# Sensors.net
KiCad netlist of a schematic drawn in Altium Designer
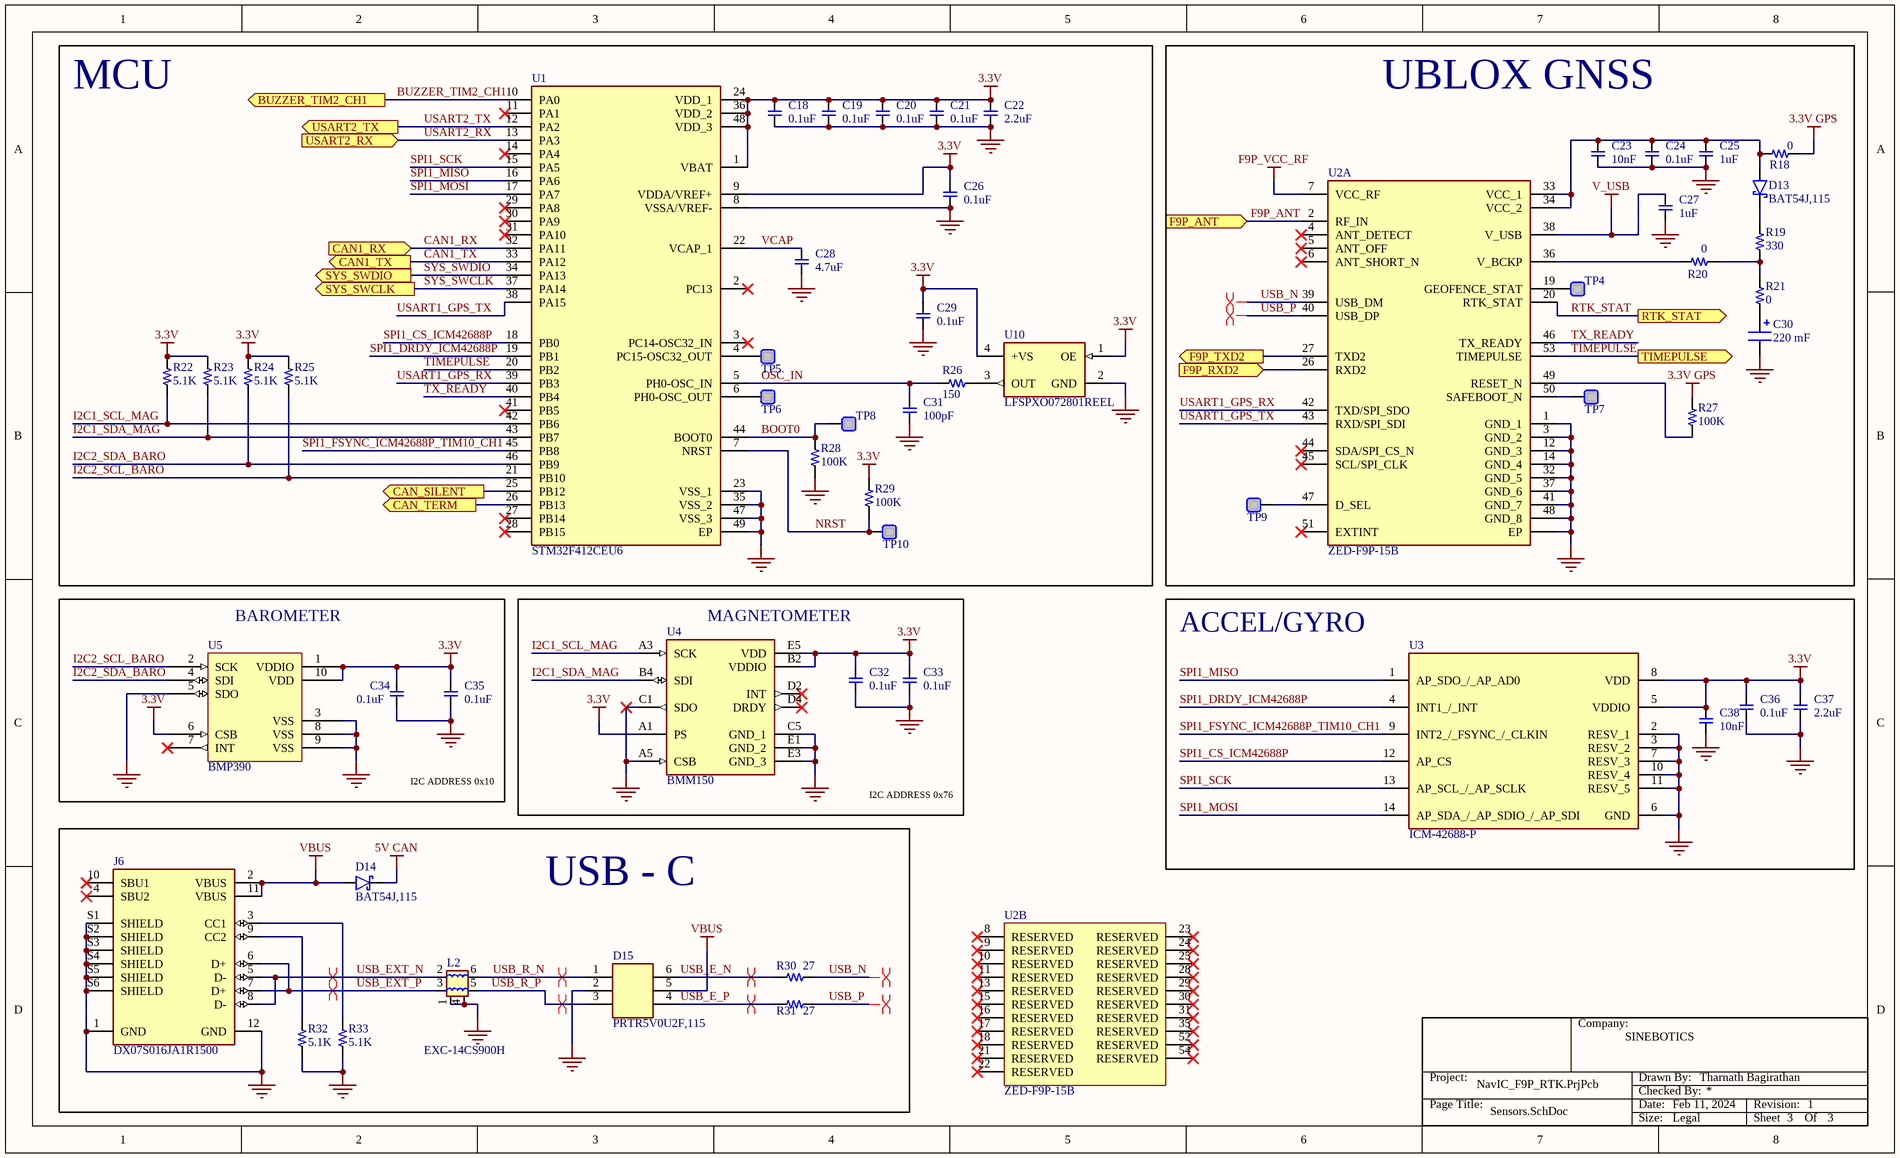
[diagram p0: Sensors.SchDoc]

(export (version "E")
  (design (tool "Eeschema 10.0.6"))
  (components
    (comp (ref "C18")
      (value "0.1uF")
      (footprint "C0402")
      (description "Capacitor 0402 Generic")
      (fields
        (field (name "MANUFACTURER PART NUMBER") "0402X104K250CT")
        (field (name "MANUFACTURER") "Walsin Technology Corporation")
      )
      (libsource (lib "Library") (part "CAP_0402"))
    )
    (comp (ref "C19")
      (value "0.1uF")
      (footprint "C0402")
      (description "Capacitor 0402 Generic")
      (fields
        (field (name "MANUFACTURER PART NUMBER") "0402X104K250CT")
        (field (name "MANUFACTURER") "Walsin Technology Corporation")
      )
      (libsource (lib "Library") (part "CAP_0402"))
    )
    (comp (ref "C20")
      (value "0.1uF")
      (footprint "C0402")
      (description "Capacitor 0402 Generic")
      (fields
        (field (name "MANUFACTURER PART NUMBER") "0402X104K250CT")
        (field (name "MANUFACTURER") "Walsin Technology Corporation")
      )
      (libsource (lib "Library") (part "CAP_0402"))
    )
    (comp (ref "C21")
      (value "0.1uF")
      (footprint "C0402")
      (description "Capacitor 0402 Generic")
      (fields
        (field (name "MANUFACTURER PART NUMBER") "0402X104K250CT")
        (field (name "MANUFACTURER") "Walsin Technology Corporation")
      )
      (libsource (lib "Library") (part "CAP_0402"))
    )
    (comp (ref "C22")
      (value "2.2uF")
      (footprint "C0402")
      (description "Capacitor 0402 Generic")
      (fields
        (field (name "MANUFACTURER PART NUMBER") "GRM155R61A225ME95D")
        (field (name "MANUFACTURER") "Murata")
      )
      (libsource (lib "Library") (part "CAP_0402"))
    )
    (comp (ref "C23")
      (value "10nF")
      (footprint "C0402")
      (description "Capacitor 0402 Generic")
      (fields
        (field (name "MANUFACTURER PART NUMBER") "CL05B103KA5NNNC")
        (field (name "MANUFACTURER") "Samsung")
      )
      (libsource (lib "Library") (part "CAP_0402"))
    )
    (comp (ref "C24")
      (value "0.1uF")
      (footprint "C0402")
      (description "Capacitor 0402 Generic")
      (fields
        (field (name "MANUFACTURER PART NUMBER") "0402X104K250CT")
        (field (name "MANUFACTURER") "Walsin Technology Corporation")
      )
      (libsource (lib "Library") (part "CAP_0402"))
    )
    (comp (ref "C25")
      (value "1uF")
      (footprint "C0402")
      (description "Capacitor 0402 Generic")
      (fields
        (field (name "MANUFACTURER PART NUMBER") "CL05A105KP5NNNC")
        (field (name "MANUFACTURER") "Samsung Electro-Mechanics")
      )
      (libsource (lib "Library") (part "CAP_0402"))
    )
    (comp (ref "C26")
      (value "0.1uF")
      (footprint "C0402")
      (description "Capacitor 0402 Generic")
      (fields
        (field (name "MANUFACTURER PART NUMBER") "0402X104K250CT")
        (field (name "MANUFACTURER") "Walsin Technology Corporation")
      )
      (libsource (lib "Library") (part "CAP_0402"))
    )
    (comp (ref "C27")
      (value "1uF")
      (footprint "C0402")
      (description "Capacitor 0402 Generic")
      (fields
        (field (name "MANUFACTURER PART NUMBER") "CL05A105KP5NNNC")
        (field (name "MANUFACTURER") "Samsung Electro-Mechanics")
      )
      (libsource (lib "Library") (part "CAP_0402"))
    )
    (comp (ref "C28")
      (value "4.7uF")
      (footprint "C0402")
      (description "Capacitor 0402 Generic")
      (fields
        (field (name "MANUFACTURER PART NUMBER") "C1005X5R0J475K050BC")
        (field (name "MANUFACTURER") "TDK Corporation")
      )
      (libsource (lib "Library") (part "CAP_0402"))
    )
    (comp (ref "C29")
      (value "0.1uF")
      (footprint "C0402")
      (description "Capacitor 0402 Generic")
      (fields
        (field (name "MANUFACTURER PART NUMBER") "0402X104K250CT")
        (field (name "MANUFACTURER") "Walsin Technology Corporation")
      )
      (libsource (lib "Library") (part "CAP_0402"))
    )
    (comp (ref "C30")
      (value "220 mF")
      (footprint "SamacSys:DSK3R3H334THL")
      (description "Capacitor Polarised")
      (fields (field (name "MANUFACTURER PART NUMBER") "DSK-3R3H224U-HL"))
      (libsource (lib "SamacSys") (part "DSK-3R3H224U-HL"))
    )
    (comp (ref "C31")
      (value "100pF")
      (footprint "C0402")
      (description "Capacitor 0402 Generic")
      (fields
        (field (name "MANUFACTURER PART NUMBER") "CL05C101JB5NNNC")
        (field (name "MANUFACTURER") "Samsung Electro-Mechanics")
      )
      (libsource (lib "Library") (part "CAP_0402"))
    )
    (comp (ref "C32")
      (value "0.1uF")
      (footprint "C0402")
      (description "Capacitor 0402 Generic")
      (fields
        (field (name "MANUFACTURER PART NUMBER") "0402X104K250CT")
        (field (name "MANUFACTURER") "Walsin Technology Corporation")
      )
      (libsource (lib "Library") (part "CAP_0402"))
    )
    (comp (ref "C33")
      (value "0.1uF")
      (footprint "C0402")
      (description "Capacitor 0402 Generic")
      (fields
        (field (name "MANUFACTURER PART NUMBER") "0402X104K250CT")
        (field (name "MANUFACTURER") "Walsin Technology Corporation")
      )
      (libsource (lib "Library") (part "CAP_0402"))
    )
    (comp (ref "C34")
      (value "0.1uF")
      (footprint "C0402")
      (description "Capacitor 0402 Generic")
      (fields
        (field (name "MANUFACTURER PART NUMBER") "0402X104K250CT")
        (field (name "MANUFACTURER") "Walsin Technology Corporation")
      )
      (libsource (lib "Library") (part "CAP_0402"))
    )
    (comp (ref "C35")
      (value "0.1uF")
      (footprint "C0402")
      (description "Capacitor 0402 Generic")
      (fields
        (field (name "MANUFACTURER PART NUMBER") "0402X104K250CT")
        (field (name "MANUFACTURER") "Walsin Technology Corporation")
      )
      (libsource (lib "Library") (part "CAP_0402"))
    )
    (comp (ref "C36")
      (value "0.1uF")
      (footprint "C0402")
      (description "Capacitor 0402 Generic")
      (fields
        (field (name "MANUFACTURER PART NUMBER") "0402X104K250CT")
        (field (name "MANUFACTURER") "Walsin Technology Corporation")
      )
      (libsource (lib "Library") (part "CAP_0402"))
    )
    (comp (ref "C37")
      (value "2.2uF")
      (footprint "C0402")
      (description "Capacitor 0402 Generic")
      (fields
        (field (name "MANUFACTURER PART NUMBER") "GRM155R61A225ME95D")
        (field (name "MANUFACTURER") "Murata")
      )
      (libsource (lib "Library") (part "CAP_0402"))
    )
    (comp (ref "C38")
      (value "10nF")
      (footprint "C0402")
      (description "Capacitor 0402 Generic")
      (fields
        (field (name "MANUFACTURER PART NUMBER") "CL05B103KA5NNNC")
        (field (name "MANUFACTURER") "Samsung")
      )
      (libsource (lib "Library") (part "CAP_0402"))
    )
    (comp (ref "D13")
      (value "BAT54J,115")
      (footprint "SamacSys:SODFL2512X80N")
      (description "Schottky Diode")
      (libsource (lib "SamacSys") (part "BAT54J,115"))
    )
    (comp (ref "D14")
      (value "BAT54J,115")
      (footprint "SamacSys:SODFL2512X80N")
      (description "Schottky Diode")
      (libsource (lib "SamacSys") (part "BAT54J,115"))
    )
    (comp (ref "D15")
      (value "PRTR5V0U2F,115")
      (footprint "SamacSys:PESD3V3L5UF115")
      (description "Diode")
      (libsource (lib "SamacSys") (part "PRTR5V0U2F,115"))
    )
    (comp (ref "J6")
      (value "DX07S016JA1R1500")
      (footprint "JAE_DX07S016JA1R1500")
      (libsource (lib "Schlib") (part "DX07S016JA1R1500"))
    )
    (comp (ref "L2")
      (value "EXC-14CS900H")
      (footprint "SamacSys:EXC14CS900H")
      (description "Filter")
      (libsource (lib "SamacSys") (part "EXC-14CS900H"))
    )
    (comp (ref "R18")
      (value "0")
      (footprint "R0402")
      (description "Resistor 0402 Generic")
      (fields
        (field (name "MANUFACTURER") "Yageo")
        (field (name "MANUFACTURER PART NUMBER") "AC0402JR-070RL")
      )
      (libsource (lib "Library") (part "RES_0402"))
    )
    (comp (ref "R19")
      (value "330")
      (footprint "R0402")
      (description "Resistor 0402 Generic")
      (fields
        (field (name "MANUFACTURER") "Yageo")
        (field (name "MANUFACTURER PART NUMBER") "RC0402FR-07330RL")
      )
      (libsource (lib "Library") (part "RES_0402"))
    )
    (comp (ref "R20")
      (value "0")
      (footprint "R0402")
      (description "Resistor 0402 Generic")
      (fields
        (field (name "MANUFACTURER") "Yageo")
        (field (name "MANUFACTURER PART NUMBER") "AC0402JR-070RL")
      )
      (libsource (lib "Library") (part "RES_0402"))
    )
    (comp (ref "R21")
      (value "0")
      (footprint "R0402")
      (description "Resistor 0402 Generic")
      (fields
        (field (name "MANUFACTURER") "Yageo")
        (field (name "MANUFACTURER PART NUMBER") "AC0402JR-070RL")
      )
      (libsource (lib "Library") (part "RES_0402"))
    )
    (comp (ref "R22")
      (value "5.1K")
      (footprint "R0402")
      (description "Resistor 0402 Generic")
      (fields
        (field (name "MANUFACTURER") "Yageo")
        (field (name "MANUFACTURER PART NUMBER") "RC0402FR-075K1L")
      )
      (libsource (lib "Library") (part "RES_0402"))
    )
    (comp (ref "R23")
      (value "5.1K")
      (footprint "R0402")
      (description "Resistor 0402 Generic")
      (fields
        (field (name "MANUFACTURER") "Yageo")
        (field (name "MANUFACTURER PART NUMBER") "RC0402FR-075K1L")
      )
      (libsource (lib "Library") (part "RES_0402"))
    )
    (comp (ref "R24")
      (value "5.1K")
      (footprint "R0402")
      (description "Resistor 0402 Generic")
      (fields
        (field (name "MANUFACTURER") "Yageo")
        (field (name "MANUFACTURER PART NUMBER") "RC0402FR-075K1L")
      )
      (libsource (lib "Library") (part "RES_0402"))
    )
    (comp (ref "R25")
      (value "5.1K")
      (footprint "R0402")
      (description "Resistor 0402 Generic")
      (fields
        (field (name "MANUFACTURER") "Yageo")
        (field (name "MANUFACTURER PART NUMBER") "RC0402FR-075K1L")
      )
      (libsource (lib "Library") (part "RES_0402"))
    )
    (comp (ref "R26")
      (value "150")
      (footprint "R0402")
      (description "Resistor 0402 Generic")
      (fields
        (field (name "MANUFACTURER") "Stackpole Electronics Inc")
        (field (name "MANUFACTURER PART NUMBER") "RC0402FR-07150RL")
      )
      (libsource (lib "Library") (part "RES_0402"))
    )
    (comp (ref "R27")
      (value "100K")
      (footprint "R0402")
      (description "Resistor 0402 Generic")
      (fields
        (field (name "MANUFACTURER") "Yageo")
        (field (name "MANUFACTURER PART NUMBER") "AC0402JR-07100KL")
      )
      (libsource (lib "Library") (part "RES_0402"))
    )
    (comp (ref "R28")
      (value "100K")
      (footprint "R0402")
      (description "Resistor 0402 Generic")
      (fields
        (field (name "MANUFACTURER") "Yageo")
        (field (name "MANUFACTURER PART NUMBER") "AC0402JR-07100KL")
      )
      (libsource (lib "Library") (part "RES_0402"))
    )
    (comp (ref "R29")
      (value "100K")
      (footprint "R0402")
      (description "Resistor 0402 Generic")
      (fields
        (field (name "MANUFACTURER") "Yageo")
        (field (name "MANUFACTURER PART NUMBER") "AC0402JR-07100KL")
      )
      (libsource (lib "Library") (part "RES_0402"))
    )
    (comp (ref "R30")
      (value "27")
      (footprint "R0402")
      (description "Resistor 0402 Generic")
      (fields
        (field (name "MANUFACTURER") "Yageo")
        (field (name "MANUFACTURER PART NUMBER") "AC0402FR-0727RL")
      )
      (libsource (lib "Library") (part "RES_0402"))
    )
    (comp (ref "R31")
      (value "27")
      (footprint "R0402")
      (description "Resistor 0402 Generic")
      (fields
        (field (name "MANUFACTURER") "Yageo")
        (field (name "MANUFACTURER PART NUMBER") "AC0402FR-0727RL")
      )
      (libsource (lib "Library") (part "RES_0402"))
    )
    (comp (ref "R32")
      (value "5.1K")
      (footprint "R0402")
      (description "Resistor 0402 Generic")
      (fields
        (field (name "MANUFACTURER") "Yageo")
        (field (name "MANUFACTURER PART NUMBER") "RC0402FR-075K1L")
      )
      (libsource (lib "Library") (part "RES_0402"))
    )
    (comp (ref "R33")
      (value "5.1K")
      (footprint "R0402")
      (description "Resistor 0402 Generic")
      (fields
        (field (name "MANUFACTURER") "Yageo")
        (field (name "MANUFACTURER PART NUMBER") "RC0402FR-075K1L")
      )
      (libsource (lib "Library") (part "RES_0402"))
    )
    (comp (ref "TP4")
      (value "TestPad")
      (footprint "TestPad")
      (description "Test Pads")
      (libsource (lib "Schlib") (part "TestPad"))
    )
    (comp (ref "TP5")
      (value "TestPad")
      (footprint "TestPad")
      (description "Test Pads")
      (libsource (lib "Schlib") (part "TestPad"))
    )
    (comp (ref "TP6")
      (value "TestPad")
      (footprint "TestPad")
      (description "Test Pads")
      (libsource (lib "Schlib") (part "TestPad"))
    )
    (comp (ref "TP7")
      (value "TestPad")
      (footprint "TestPad")
      (description "Test Pads")
      (libsource (lib "Schlib") (part "TestPad"))
    )
    (comp (ref "TP8")
      (value "TestPad")
      (footprint "TestPad")
      (description "Test Pads")
      (libsource (lib "Schlib") (part "TestPad"))
    )
    (comp (ref "TP9")
      (value "TestPad")
      (footprint "TestPad")
      (description "Test Pads")
      (libsource (lib "Schlib") (part "TestPad"))
    )
    (comp (ref "TP10")
      (value "TestPad")
      (footprint "TestPad")
      (description "Test Pads")
      (libsource (lib "Schlib") (part "TestPad"))
    )
    (comp (ref "U1")
      (value "STM32F412CEU6")
      (footprint "QFN50P700X700X65-49N-D")
      (description "ARM Microcontrollers - MCU 16/32-BITS MICROS")
      (libsource (lib "Schlib") (part "STM32F412CEU6"))
    )
    (comp (ref "U2")
      (value "ZED-F9P-15B")
      (footprint "ZEDF9P15B")
      (description "Ublox F9P-15B Dual Band GNSS Receiver")
      (libsource (lib "Schlib") (part "ZED-F9P-15B"))
    )
    (comp (ref "U3")
      (value "ICM-42688-P")
      (footprint "SamacSys:IIM42352")
      (description "Integrated Circuit")
      (libsource (lib "SamacSys") (part "ICM-42688-P"))
    )
    (comp (ref "U4")
      (value "BMM150")
      (footprint "SamacSys:BMM150")
      (description "Integrated Circuit")
      (libsource (lib "SamacSys") (part "BMM150"))
    )
    (comp (ref "U5")
      (value "BMP390")
      (footprint "BMP390")
      (description "Bosch Sensortec BMP390 Barometer")
      (fields (field (name "MANUFACTURER") "Bosch Sensortec"))
      (libsource (lib "Schlib") (part "BMP390"))
    )
    (comp (ref "U10")
      (value "LFSPXO072801REEL")
      (footprint "SamacSys:LFSPXO072801REEL")
      (description "Crystal or Oscillator")
      (libsource (lib "SamacSys") (part "LFSPXO072801REEL"))
    )
  )
  (nets
    (net (code "1") (name "/BOOT0") (class "Default")
      (node (ref "R28") (pin "2") (pintype "passive"))
      (node (ref "TP8") (pin "1") (pinfunction "1_1") (pintype "passive"))
      (node (ref "U1") (pin "44") (pinfunction "BOOT0_44") (pintype "passive"))
    )
    (net (code "2") (name "/BUZZER_TIM2_CH1") (class "Default")
      (node (ref "U1") (pin "10") (pinfunction "PA0_10") (pintype "passive"))
    )
    (net (code "3") (name "/CAN1_RX") (class "Default")
      (node (ref "U1") (pin "32") (pinfunction "PA11_32") (pintype "passive"))
    )
    (net (code "4") (name "/CAN1_TX") (class "Default")
      (node (ref "U1") (pin "33") (pinfunction "PA12_33") (pintype "passive"))
    )
    (net (code "5") (name "/CAN_SILENT") (class "Default")
      (node (ref "U1") (pin "25") (pinfunction "PB12_25") (pintype "passive"))
    )
    (net (code "6") (name "/CAN_TERM") (class "Default")
      (node (ref "U1") (pin "26") (pinfunction "PB13_26") (pintype "passive"))
    )
    (net (code "7") (name "/F9P_ANT") (class "Default")
      (node (ref "U2") (pin "2") (pinfunction "RF_IN_2") (pintype "passive"))
    )
    (net (code "8") (name "/F9P_RXD2") (class "Default")
      (node (ref "U2") (pin "26") (pinfunction "RXD2_26") (pintype "passive"))
    )
    (net (code "9") (name "/F9P_TXD2") (class "Default")
      (node (ref "U2") (pin "27") (pinfunction "TXD2_27") (pintype "passive"))
    )
    (net (code "10") (name "/I2C1_SCL_MAG") (class "Default")
      (node (ref "R22") (pin "1") (pintype "passive"))
      (node (ref "U1") (pin "42") (pinfunction "PB6_42") (pintype "passive"))
      (node (ref "U4") (pin "A3") (pinfunction "SCK_A3") (pintype "input"))
    )
    (net (code "11") (name "/I2C1_SDA_MAG") (class "Default")
      (node (ref "R23") (pin "1") (pintype "passive"))
      (node (ref "U1") (pin "43") (pinfunction "PB7_43") (pintype "passive"))
      (node (ref "U4") (pin "B4") (pinfunction "SDI_B4") (pintype "bidirectional"))
    )
    (net (code "12") (name "/I2C2_SCL_BARO") (class "Default")
      (node (ref "R25") (pin "1") (pintype "passive"))
      (node (ref "U1") (pin "21") (pinfunction "PB10_21") (pintype "passive"))
      (node (ref "U5") (pin "2") (pinfunction "SCK_2") (pintype "input"))
    )
    (net (code "13") (name "/I2C2_SDA_BARO") (class "Default")
      (node (ref "R24") (pin "1") (pintype "passive"))
      (node (ref "U1") (pin "46") (pinfunction "PB9_46") (pintype "passive"))
      (node (ref "U5") (pin "4") (pinfunction "SDI_4") (pintype "bidirectional"))
    )
    (net (code "14") (name "/NRST") (class "Default")
      (node (ref "R29") (pin "1") (pintype "passive"))
      (node (ref "TP10") (pin "1") (pinfunction "1_1") (pintype "passive"))
      (node (ref "U1") (pin "7") (pinfunction "NRST_7") (pintype "passive"))
    )
    (net (code "15") (name "/OSC_IN") (class "Default")
      (node (ref "C31") (pin "2") (pintype "passive"))
      (node (ref "R26") (pin "2") (pintype "passive"))
      (node (ref "U1") (pin "5") (pinfunction "PH0-OSC_IN_5") (pintype "passive"))
    )
    (net (code "16") (name "/RTK_STAT") (class "Default")
      (node (ref "U2") (pin "20") (pinfunction "RTK_STAT_20") (pintype "passive"))
    )
    (net (code "17") (name "/SPI1_CS_ICM42688P") (class "Default")
      (node (ref "U1") (pin "18") (pinfunction "PB0_18") (pintype "passive"))
      (node (ref "U3") (pin "12") (pinfunction "AP_CS_12") (pintype "passive"))
    )
    (net (code "18") (name "/SPI1_DRDY_ICM42688P") (class "Default")
      (node (ref "U1") (pin "19") (pinfunction "PB1_19") (pintype "passive"))
      (node (ref "U3") (pin "4") (pinfunction "INT1_/_INT_4") (pintype "passive"))
    )
    (net (code "19") (name "/SPI1_FSYNC_ICM42688P_TIM10_CH1") (class "Default")
      (node (ref "U1") (pin "45") (pinfunction "PB8_45") (pintype "passive"))
      (node (ref "U3") (pin "9") (pinfunction "INT2_/_FSYNC_/_CLKIN_9") (pintype "passive"))
    )
    (net (code "20") (name "/SPI1_MISO") (class "Default")
      (node (ref "U1") (pin "16") (pinfunction "PA6_16") (pintype "passive"))
      (node (ref "U3") (pin "1") (pinfunction "AP_SDO_/_AP_AD0_1") (pintype "passive"))
    )
    (net (code "21") (name "/SPI1_MOSI") (class "Default")
      (node (ref "U1") (pin "17") (pinfunction "PA7_17") (pintype "passive"))
      (node (ref "U3") (pin "14") (pinfunction "AP_SDA_/_AP_SDIO_/_AP_SDI_14") (pintype "passive"))
    )
    (net (code "22") (name "/SPI1_SCK") (class "Default")
      (node (ref "U1") (pin "15") (pinfunction "PA5_15") (pintype "passive"))
      (node (ref "U3") (pin "13") (pinfunction "AP_SCL_/_AP_SCLK_13") (pintype "passive"))
    )
    (net (code "23") (name "/SYS_SWCLK") (class "Default")
      (node (ref "U1") (pin "37") (pinfunction "PA14_37") (pintype "passive"))
    )
    (net (code "24") (name "/SYS_SWDIO") (class "Default")
      (node (ref "U1") (pin "34") (pinfunction "PA13_34") (pintype "passive"))
    )
    (net (code "25") (name "/TIMEPULSE") (class "Default")
      (node (ref "U1") (pin "20") (pinfunction "PB2_20") (pintype "passive"))
      (node (ref "U2") (pin "53") (pinfunction "TIMEPULSE_53") (pintype "passive"))
    )
    (net (code "26") (name "/TX_READY") (class "Default")
      (node (ref "U1") (pin "40") (pinfunction "PB4_40") (pintype "passive"))
      (node (ref "U2") (pin "46") (pinfunction "TX_READY_46") (pintype "passive"))
    )
    (net (code "27") (name "/USART1_GPS_RX") (class "Default")
      (node (ref "U1") (pin "39") (pinfunction "PB3_39") (pintype "passive"))
      (node (ref "U2") (pin "42") (pinfunction "TXD/SPI_SDO_42") (pintype "passive"))
    )
    (net (code "28") (name "/USART1_GPS_TX") (class "Default")
      (node (ref "U1") (pin "38") (pinfunction "PA15_38") (pintype "passive"))
      (node (ref "U2") (pin "43") (pinfunction "RXD/SPI_SDI_43") (pintype "passive"))
    )
    (net (code "29") (name "/USART2_RX") (class "Default")
      (node (ref "U1") (pin "13") (pinfunction "PA3_13") (pintype "passive"))
    )
    (net (code "30") (name "/USART2_TX") (class "Default")
      (node (ref "U1") (pin "12") (pinfunction "PA2_12") (pintype "passive"))
    )
    (net (code "31") (name "/USB_EXT_N") (class "Default")
      (node (ref "J6") (pin "5") (pinfunction "D-_5") (pintype "bidirectional"))
      (node (ref "J6") (pin "8") (pinfunction "D-_8") (pintype "bidirectional"))
      (node (ref "L2") (pin "2") (pinfunction "COIL_1_2") (pintype "passive"))
    )
    (net (code "32") (name "/USB_EXT_P") (class "Default")
      (node (ref "J6") (pin "6") (pinfunction "D+_6") (pintype "bidirectional"))
      (node (ref "J6") (pin "7") (pinfunction "D+_7") (pintype "bidirectional"))
      (node (ref "L2") (pin "3") (pinfunction "COIL_2_3") (pintype "passive"))
    )
    (net (code "33") (name "/USB_E_N") (class "Default")
      (node (ref "D15") (pin "6") (pinfunction "input/output_1_2_6") (pintype "passive"))
      (node (ref "R30") (pin "1") (pintype "passive"))
    )
    (net (code "34") (name "/USB_E_P") (class "Default")
      (node (ref "D15") (pin "4") (pinfunction "input/output_2_2_4") (pintype "passive"))
      (node (ref "R31") (pin "2") (pintype "passive"))
    )
    (net (code "35") (name "/USB_N") (class "Default")
      (node (ref "R30") (pin "2") (pintype "passive"))
      (node (ref "U2") (pin "39") (pinfunction "USB_DM_39") (pintype "passive"))
    )
    (net (code "36") (name "/USB_P") (class "Default")
      (node (ref "R31") (pin "1") (pintype "passive"))
      (node (ref "U2") (pin "40") (pinfunction "USB_DP_40") (pintype "passive"))
    )
    (net (code "37") (name "/USB_R_N") (class "Default")
      (node (ref "D15") (pin "1") (pinfunction "input/output_1_1_1") (pintype "passive"))
      (node (ref "L2") (pin "6") (pinfunction "COIL_4_6") (pintype "passive"))
    )
    (net (code "38") (name "/USB_R_P") (class "Default")
      (node (ref "D15") (pin "3") (pinfunction "input/output_2_1_3") (pintype "passive"))
      (node (ref "L2") (pin "5") (pinfunction "COIL_3_5") (pintype "passive"))
    )
    (net (code "39") (name "/VCAP") (class "Default")
      (node (ref "C28") (pin "2") (pintype "passive"))
      (node (ref "U1") (pin "22") (pinfunction "VCAP_1_22") (pintype "passive"))
    )
    (net (code "40") (name "3.3V") (class "Default")
      (node (ref "C18") (pin "2") (pintype "passive"))
      (node (ref "C19") (pin "2") (pintype "passive"))
      (node (ref "C20") (pin "2") (pintype "passive"))
      (node (ref "C21") (pin "2") (pintype "passive"))
      (node (ref "C22") (pin "2") (pintype "passive"))
      (node (ref "C26") (pin "2") (pintype "passive"))
      (node (ref "C29") (pin "2") (pintype "passive"))
      (node (ref "C32") (pin "2") (pintype "passive"))
      (node (ref "C33") (pin "2") (pintype "passive"))
      (node (ref "C34") (pin "2") (pintype "passive"))
      (node (ref "C35") (pin "2") (pintype "passive"))
      (node (ref "C36") (pin "2") (pintype "passive"))
      (node (ref "C37") (pin "2") (pintype "passive"))
      (node (ref "C38") (pin "2") (pintype "passive"))
      (node (ref "R22") (pin "2") (pintype "passive"))
      (node (ref "R23") (pin "2") (pintype "passive"))
      (node (ref "R24") (pin "2") (pintype "passive"))
      (node (ref "R25") (pin "2") (pintype "passive"))
      (node (ref "R29") (pin "2") (pintype "passive"))
      (node (ref "U1") (pin "1") (pinfunction "VBAT_1") (pintype "passive"))
      (node (ref "U1") (pin "24") (pinfunction "VDD_1_24") (pintype "passive"))
      (node (ref "U1") (pin "36") (pinfunction "VDD_2_36") (pintype "passive"))
      (node (ref "U1") (pin "48") (pinfunction "VDD_3_48") (pintype "passive"))
      (node (ref "U1") (pin "9") (pinfunction "VDDA/VREF+_9") (pintype "passive"))
      (node (ref "U10") (pin "1") (pinfunction "OE_1") (pintype "input"))
      (node (ref "U10") (pin "4") (pinfunction "+VS_4") (pintype "passive"))
      (node (ref "U3") (pin "5") (pinfunction "VDDIO_5") (pintype "passive"))
      (node (ref "U3") (pin "8") (pinfunction "VDD_8") (pintype "passive"))
      (node (ref "U4") (pin "A1") (pinfunction "PS_A1") (pintype "passive"))
      (node (ref "U4") (pin "B2") (pinfunction "VDDIO_B2") (pintype "passive"))
      (node (ref "U4") (pin "E5") (pinfunction "VDD_E5") (pintype "passive"))
      (node (ref "U5") (pin "1") (pinfunction "VDDIO_1") (pintype "power_in"))
      (node (ref "U5") (pin "10") (pinfunction "VDD_10") (pintype "power_in"))
      (node (ref "U5") (pin "6") (pinfunction "CSB_6") (pintype "input"))
    )
    (net (code "41") (name "3.3V GPS") (class "Default")
      (node (ref "R18") (pin "2") (pintype "passive"))
      (node (ref "R27") (pin "2") (pintype "passive"))
    )
    (net (code "42") (name "5V CAN") (class "Default")
      (node (ref "D14") (pin "1") (pinfunction "K_1") (pintype "passive"))
    )
    (net (code "43") (name "F9P_VCC_RF") (class "Default")
      (node (ref "U2") (pin "7") (pinfunction "VCC_RF_7") (pintype "passive"))
    )
    (net (code "44") (name "GND") (class "Default")
      (node (ref "C18") (pin "1") (pintype "passive"))
      (node (ref "C19") (pin "1") (pintype "passive"))
      (node (ref "C20") (pin "1") (pintype "passive"))
      (node (ref "C21") (pin "1") (pintype "passive"))
      (node (ref "C22") (pin "1") (pintype "passive"))
      (node (ref "C23") (pin "1") (pintype "passive"))
      (node (ref "C24") (pin "1") (pintype "passive"))
      (node (ref "C25") (pin "1") (pintype "passive"))
      (node (ref "C26") (pin "1") (pintype "passive"))
      (node (ref "C27") (pin "1") (pintype "passive"))
      (node (ref "C28") (pin "1") (pintype "passive"))
      (node (ref "C29") (pin "1") (pintype "passive"))
      (node (ref "C30") (pin "2") (pinfunction "-_2") (pintype "passive"))
      (node (ref "C31") (pin "1") (pintype "passive"))
      (node (ref "C32") (pin "1") (pintype "passive"))
      (node (ref "C33") (pin "1") (pintype "passive"))
      (node (ref "C34") (pin "1") (pintype "passive"))
      (node (ref "C35") (pin "1") (pintype "passive"))
      (node (ref "C36") (pin "1") (pintype "passive"))
      (node (ref "C37") (pin "1") (pintype "passive"))
      (node (ref "C38") (pin "1") (pintype "passive"))
      (node (ref "D15") (pin "2") (pinfunction "ground_2") (pintype "passive"))
      (node (ref "J6") (pin "1") (pinfunction "GND_1") (pintype "power_in"))
      (node (ref "J6") (pin "12") (pinfunction "GND_12") (pintype "power_in"))
      (node (ref "J6") (pin "S1") (pinfunction "SHIELD_S1") (pintype "passive"))
      (node (ref "J6") (pin "S2") (pinfunction "SHIELD_S2") (pintype "passive"))
      (node (ref "J6") (pin "S3") (pinfunction "SHIELD_S3") (pintype "passive"))
      (node (ref "J6") (pin "S4") (pinfunction "SHIELD_S4") (pintype "passive"))
      (node (ref "J6") (pin "S5") (pinfunction "SHIELD_S5") (pintype "passive"))
      (node (ref "J6") (pin "S6") (pinfunction "SHIELD_S6") (pintype "passive"))
      (node (ref "L2") (pin "1") (pinfunction "GND_1_1") (pintype "passive"))
      (node (ref "L2") (pin "4") (pinfunction "GND_2_4") (pintype "passive"))
      (node (ref "R28") (pin "1") (pintype "passive"))
      (node (ref "R32") (pin "1") (pintype "passive"))
      (node (ref "R33") (pin "1") (pintype "passive"))
      (node (ref "U1") (pin "23") (pinfunction "VSS_1_23") (pintype "passive"))
      (node (ref "U1") (pin "35") (pinfunction "VSS_2_35") (pintype "passive"))
      (node (ref "U1") (pin "47") (pinfunction "VSS_3_47") (pintype "passive"))
      (node (ref "U1") (pin "49") (pinfunction "EP_49") (pintype "passive"))
      (node (ref "U1") (pin "8") (pinfunction "VSSA/VREF-_8") (pintype "passive"))
      (node (ref "U10") (pin "2") (pinfunction "GND_2") (pintype "passive"))
      (node (ref "U2") (pin "1") (pinfunction "GND_1_1") (pintype "passive"))
      (node (ref "U2") (pin "12") (pinfunction "GND_3_12") (pintype "passive"))
      (node (ref "U2") (pin "14") (pinfunction "GND_4_14") (pintype "passive"))
      (node (ref "U2") (pin "3") (pinfunction "GND_2_3") (pintype "passive"))
      (node (ref "U2") (pin "32") (pinfunction "GND_5_32") (pintype "passive"))
      (node (ref "U2") (pin "37") (pinfunction "GND_6_37") (pintype "passive"))
      (node (ref "U2") (pin "41") (pinfunction "GND_7_41") (pintype "passive"))
      (node (ref "U2") (pin "48") (pinfunction "GND_8_48") (pintype "passive"))
      (node (ref "U2") (pin "55") (pinfunction "EP_55") (pintype "passive"))
      (node (ref "U3") (pin "10") (pinfunction "RESV_4_10") (pintype "passive"))
      (node (ref "U3") (pin "11") (pinfunction "RESV_5_11") (pintype "passive"))
      (node (ref "U3") (pin "2") (pinfunction "RESV_1_2") (pintype "passive"))
      (node (ref "U3") (pin "3") (pinfunction "RESV_2_3") (pintype "passive"))
      (node (ref "U3") (pin "6") (pinfunction "GND_6") (pintype "passive"))
      (node (ref "U3") (pin "7") (pinfunction "RESV_3_7") (pintype "passive"))
      (node (ref "U4") (pin "A5") (pinfunction "CSB_A5") (pintype "input"))
      (node (ref "U4") (pin "C1") (pinfunction "SDO_C1") (pintype "output"))
      (node (ref "U4") (pin "C5") (pinfunction "GND_1_C5") (pintype "passive"))
      (node (ref "U4") (pin "E1") (pinfunction "GND_2_E1") (pintype "passive"))
      (node (ref "U4") (pin "E3") (pinfunction "GND_3_E3") (pintype "passive"))
      (node (ref "U5") (pin "3") (pinfunction "VSS_3") (pintype "power_in"))
      (node (ref "U5") (pin "5") (pinfunction "SDO_5") (pintype "bidirectional"))
      (node (ref "U5") (pin "8") (pinfunction "VSS_8") (pintype "power_in"))
      (node (ref "U5") (pin "9") (pinfunction "VSS_9") (pintype "power_in"))
    )
    (net (code "45") (name "Net-(C30-+)") (class "Default")
      (node (ref "C30") (pin "1") (pinfunction "+_1") (pintype "passive"))
      (node (ref "R21") (pin "1") (pintype "passive"))
    )
    (net (code "46") (name "Net-(D13-A)") (class "Default")
      (node (ref "C23") (pin "2") (pintype "passive"))
      (node (ref "C24") (pin "2") (pintype "passive"))
      (node (ref "C25") (pin "2") (pintype "passive"))
      (node (ref "D13") (pin "2") (pinfunction "A_2") (pintype "passive"))
      (node (ref "R18") (pin "1") (pintype "passive"))
      (node (ref "U2") (pin "33") (pinfunction "VCC_1_33") (pintype "passive"))
      (node (ref "U2") (pin "34") (pinfunction "VCC_2_34") (pintype "passive"))
    )
    (net (code "47") (name "Net-(D13-K)") (class "Default")
      (node (ref "D13") (pin "1") (pinfunction "K_1") (pintype "passive"))
      (node (ref "R19") (pin "2") (pintype "passive"))
    )
    (net (code "48") (name "Net-(J6-CC1)") (class "Default")
      (node (ref "J6") (pin "3") (pinfunction "CC1_3") (pintype "bidirectional"))
      (node (ref "R33") (pin "2") (pintype "passive"))
    )
    (net (code "49") (name "Net-(J6-CC2)") (class "Default")
      (node (ref "J6") (pin "9") (pinfunction "CC2_9") (pintype "bidirectional"))
      (node (ref "R32") (pin "2") (pintype "passive"))
    )
    (net (code "50") (name "Net-(R19-Pad1)") (class "Default")
      (node (ref "R19") (pin "1") (pintype "passive"))
      (node (ref "R20") (pin "2") (pintype "passive"))
      (node (ref "R21") (pin "2") (pintype "passive"))
    )
    (net (code "51") (name "Net-(U1-PC15-OSC32_OUT)") (class "Default")
      (node (ref "TP5") (pin "1") (pinfunction "1_1") (pintype "passive"))
      (node (ref "U1") (pin "4") (pinfunction "PC15-OSC32_OUT_4") (pintype "passive"))
    )
    (net (code "52") (name "Net-(U1-PH0-OSC_OUT)") (class "Default")
      (node (ref "TP6") (pin "1") (pinfunction "1_1") (pintype "passive"))
      (node (ref "U1") (pin "6") (pinfunction "PH0-OSC_OUT_6") (pintype "passive"))
    )
    (net (code "53") (name "Net-(U2A-D_SEL)") (class "Default")
      (node (ref "TP9") (pin "1") (pinfunction "1_1") (pintype "passive"))
      (node (ref "U2") (pin "47") (pinfunction "D_SEL_47") (pintype "passive"))
    )
    (net (code "54") (name "Net-(U2A-GEOFENCE_STAT)") (class "Default")
      (node (ref "TP4") (pin "1") (pinfunction "1_1") (pintype "passive"))
      (node (ref "U2") (pin "19") (pinfunction "GEOFENCE_STAT_19") (pintype "passive"))
    )
    (net (code "55") (name "Net-(U2A-RESET_N)") (class "Default")
      (node (ref "R27") (pin "1") (pintype "passive"))
      (node (ref "U2") (pin "49") (pinfunction "RESET_N_49") (pintype "passive"))
    )
    (net (code "56") (name "Net-(U2A-SAFEBOOT_N)") (class "Default")
      (node (ref "TP7") (pin "1") (pinfunction "1_1") (pintype "passive"))
      (node (ref "U2") (pin "50") (pinfunction "SAFEBOOT_N_50") (pintype "passive"))
    )
    (net (code "57") (name "Net-(U2A-V_BCKP)") (class "Default")
      (node (ref "R20") (pin "1") (pintype "passive"))
      (node (ref "U2") (pin "36") (pinfunction "V_BCKP_36") (pintype "passive"))
    )
    (net (code "58") (name "Net-(U10-OUT)") (class "Default")
      (node (ref "R26") (pin "1") (pintype "passive"))
      (node (ref "U10") (pin "3") (pinfunction "OUT_3") (pintype "output"))
    )
    (net (code "59") (name "VBUS") (class "Default")
      (node (ref "D14") (pin "2") (pinfunction "A_2") (pintype "passive"))
      (node (ref "D15") (pin "5") (pinfunction "supply_voltage_5") (pintype "passive"))
      (node (ref "J6") (pin "11") (pinfunction "VBUS_11") (pintype "power_in"))
      (node (ref "J6") (pin "2") (pinfunction "VBUS_2") (pintype "power_in"))
    )
    (net (code "60") (name "V_USB") (class "Default")
      (node (ref "C27") (pin "2") (pintype "passive"))
      (node (ref "U2") (pin "38") (pinfunction "V_USB_38") (pintype "passive"))
    )
    (net (code "61") (name "unconnected-(J6-SBU1-Pad10)") (class "Default")
      (node (ref "J6") (pin "10") (pinfunction "SBU1_10") (pintype "passive+no_connect"))
    )
    (net (code "62") (name "unconnected-(J6-SBU2-Pad4)") (class "Default")
      (node (ref "J6") (pin "4") (pinfunction "SBU2_4") (pintype "passive+no_connect"))
    )
    (net (code "63") (name "unconnected-(U1-PA1-Pad11)") (class "Default")
      (node (ref "U1") (pin "11") (pinfunction "PA1_11") (pintype "passive+no_connect"))
    )
    (net (code "64") (name "unconnected-(U1-PA4-Pad14)") (class "Default")
      (node (ref "U1") (pin "14") (pinfunction "PA4_14") (pintype "passive+no_connect"))
    )
    (net (code "65") (name "unconnected-(U1-PA8-Pad29)") (class "Default")
      (node (ref "U1") (pin "29") (pinfunction "PA8_29") (pintype "passive+no_connect"))
    )
    (net (code "66") (name "unconnected-(U1-PA9-Pad30)") (class "Default")
      (node (ref "U1") (pin "30") (pinfunction "PA9_30") (pintype "passive+no_connect"))
    )
    (net (code "67") (name "unconnected-(U1-PA10-Pad31)") (class "Default")
      (node (ref "U1") (pin "31") (pinfunction "PA10_31") (pintype "passive+no_connect"))
    )
    (net (code "68") (name "unconnected-(U1-PB5-Pad41)") (class "Default")
      (node (ref "U1") (pin "41") (pinfunction "PB5_41") (pintype "passive+no_connect"))
    )
    (net (code "69") (name "unconnected-(U1-PB14-Pad27)") (class "Default")
      (node (ref "U1") (pin "27") (pinfunction "PB14_27") (pintype "passive+no_connect"))
    )
    (net (code "70") (name "unconnected-(U1-PB15-Pad28)") (class "Default")
      (node (ref "U1") (pin "28") (pinfunction "PB15_28") (pintype "passive+no_connect"))
    )
    (net (code "71") (name "unconnected-(U1-PC13-Pad2)") (class "Default")
      (node (ref "U1") (pin "2") (pinfunction "PC13_2") (pintype "passive+no_connect"))
    )
    (net (code "72") (name "unconnected-(U1-PC14-OSC32_IN-Pad3)") (class "Default")
      (node (ref "U1") (pin "3") (pinfunction "PC14-OSC32_IN_3") (pintype "passive+no_connect"))
    )
    (net (code "73") (name "unconnected-(U2A-ANT_DETECT-Pad4)") (class "Default")
      (node (ref "U2") (pin "4") (pinfunction "ANT_DETECT_4") (pintype "passive+no_connect"))
    )
    (net (code "74") (name "unconnected-(U2A-ANT_OFF-Pad5)") (class "Default")
      (node (ref "U2") (pin "5") (pinfunction "ANT_OFF_5") (pintype "passive+no_connect"))
    )
    (net (code "75") (name "unconnected-(U2A-ANT_SHORT_N-Pad6)") (class "Default")
      (node (ref "U2") (pin "6") (pinfunction "ANT_SHORT_N_6") (pintype "passive+no_connect"))
    )
    (net (code "76") (name "unconnected-(U2A-EXTINT-Pad51)") (class "Default")
      (node (ref "U2") (pin "51") (pinfunction "EXTINT_51") (pintype "passive+no_connect"))
    )
    (net (code "77") (name "unconnected-(U2A-SCL{slash}SPI_CLK-Pad45)") (class "Default")
      (node (ref "U2") (pin "45") (pinfunction "SCL/SPI_CLK_45") (pintype "passive+no_connect"))
    )
    (net (code "78") (name "unconnected-(U2A-SDA{slash}SPI_CS_N-Pad44)") (class "Default")
      (node (ref "U2") (pin "44") (pinfunction "SDA/SPI_CS_N_44") (pintype "passive+no_connect"))
    )
    (net (code "79") (name "unconnected-(U2B-RESERVED-Pad8)") (class "Default")
      (node (ref "U2") (pin "8") (pinfunction "RESERVED_8") (pintype "passive+no_connect"))
    )
    (net (code "80") (name "unconnected-(U2B-RESERVED-Pad9)") (class "Default")
      (node (ref "U2") (pin "9") (pinfunction "RESERVED_9") (pintype "passive+no_connect"))
    )
    (net (code "81") (name "unconnected-(U2B-RESERVED-Pad10)") (class "Default")
      (node (ref "U2") (pin "10") (pinfunction "RESERVED_10") (pintype "passive+no_connect"))
    )
    (net (code "82") (name "unconnected-(U2B-RESERVED-Pad11)") (class "Default")
      (node (ref "U2") (pin "11") (pinfunction "RESERVED_11") (pintype "passive+no_connect"))
    )
    (net (code "83") (name "unconnected-(U2B-RESERVED-Pad13)") (class "Default")
      (node (ref "U2") (pin "13") (pinfunction "RESERVED_13") (pintype "passive+no_connect"))
    )
    (net (code "84") (name "unconnected-(U2B-RESERVED-Pad15)") (class "Default")
      (node (ref "U2") (pin "15") (pinfunction "RESERVED_15") (pintype "passive+no_connect"))
    )
    (net (code "85") (name "unconnected-(U2B-RESERVED-Pad16)") (class "Default")
      (node (ref "U2") (pin "16") (pinfunction "RESERVED_16") (pintype "passive+no_connect"))
    )
    (net (code "86") (name "unconnected-(U2B-RESERVED-Pad17)") (class "Default")
      (node (ref "U2") (pin "17") (pinfunction "RESERVED_17") (pintype "passive+no_connect"))
    )
    (net (code "87") (name "unconnected-(U2B-RESERVED-Pad18)") (class "Default")
      (node (ref "U2") (pin "18") (pinfunction "RESERVED_18") (pintype "passive+no_connect"))
    )
    (net (code "88") (name "unconnected-(U2B-RESERVED-Pad21)") (class "Default")
      (node (ref "U2") (pin "21") (pinfunction "RESERVED_21") (pintype "passive+no_connect"))
    )
    (net (code "89") (name "unconnected-(U2B-RESERVED-Pad22)") (class "Default")
      (node (ref "U2") (pin "22") (pinfunction "RESERVED_22") (pintype "passive+no_connect"))
    )
    (net (code "90") (name "unconnected-(U2B-RESERVED-Pad23)") (class "Default")
      (node (ref "U2") (pin "23") (pinfunction "RESERVED_23") (pintype "passive+no_connect"))
    )
    (net (code "91") (name "unconnected-(U2B-RESERVED-Pad24)") (class "Default")
      (node (ref "U2") (pin "24") (pinfunction "RESERVED_24") (pintype "passive+no_connect"))
    )
    (net (code "92") (name "unconnected-(U2B-RESERVED-Pad25)") (class "Default")
      (node (ref "U2") (pin "25") (pinfunction "RESERVED_25") (pintype "passive+no_connect"))
    )
    (net (code "93") (name "unconnected-(U2B-RESERVED-Pad28)") (class "Default")
      (node (ref "U2") (pin "28") (pinfunction "RESERVED_28") (pintype "passive+no_connect"))
    )
    (net (code "94") (name "unconnected-(U2B-RESERVED-Pad29)") (class "Default")
      (node (ref "U2") (pin "29") (pinfunction "RESERVED_29") (pintype "passive+no_connect"))
    )
    (net (code "95") (name "unconnected-(U2B-RESERVED-Pad30)") (class "Default")
      (node (ref "U2") (pin "30") (pinfunction "RESERVED_30") (pintype "passive+no_connect"))
    )
    (net (code "96") (name "unconnected-(U2B-RESERVED-Pad31)") (class "Default")
      (node (ref "U2") (pin "31") (pinfunction "RESERVED_31") (pintype "passive+no_connect"))
    )
    (net (code "97") (name "unconnected-(U2B-RESERVED-Pad35)") (class "Default")
      (node (ref "U2") (pin "35") (pinfunction "RESERVED_35") (pintype "passive+no_connect"))
    )
    (net (code "98") (name "unconnected-(U2B-RESERVED-Pad52)") (class "Default")
      (node (ref "U2") (pin "52") (pinfunction "RESERVED_52") (pintype "passive+no_connect"))
    )
    (net (code "99") (name "unconnected-(U2B-RESERVED-Pad54)") (class "Default")
      (node (ref "U2") (pin "54") (pinfunction "RESERVED_54") (pintype "passive+no_connect"))
    )
    (net (code "100") (name "unconnected-(U4-DRDY-PadD4)") (class "Default")
      (node (ref "U4") (pin "D4") (pinfunction "DRDY_D4") (pintype "output+no_connect"))
    )
    (net (code "101") (name "unconnected-(U4-INT-PadD2)") (class "Default")
      (node (ref "U4") (pin "D2") (pinfunction "INT_D2") (pintype "output+no_connect"))
    )
    (net (code "102") (name "unconnected-(U5-INT-Pad7)") (class "Default")
      (node (ref "U5") (pin "7") (pinfunction "INT_7") (pintype "output+no_connect"))
    )
  )
)
